# LT8315TestBoard.net
KiCad netlist of a schematic drawn in Altium Designer
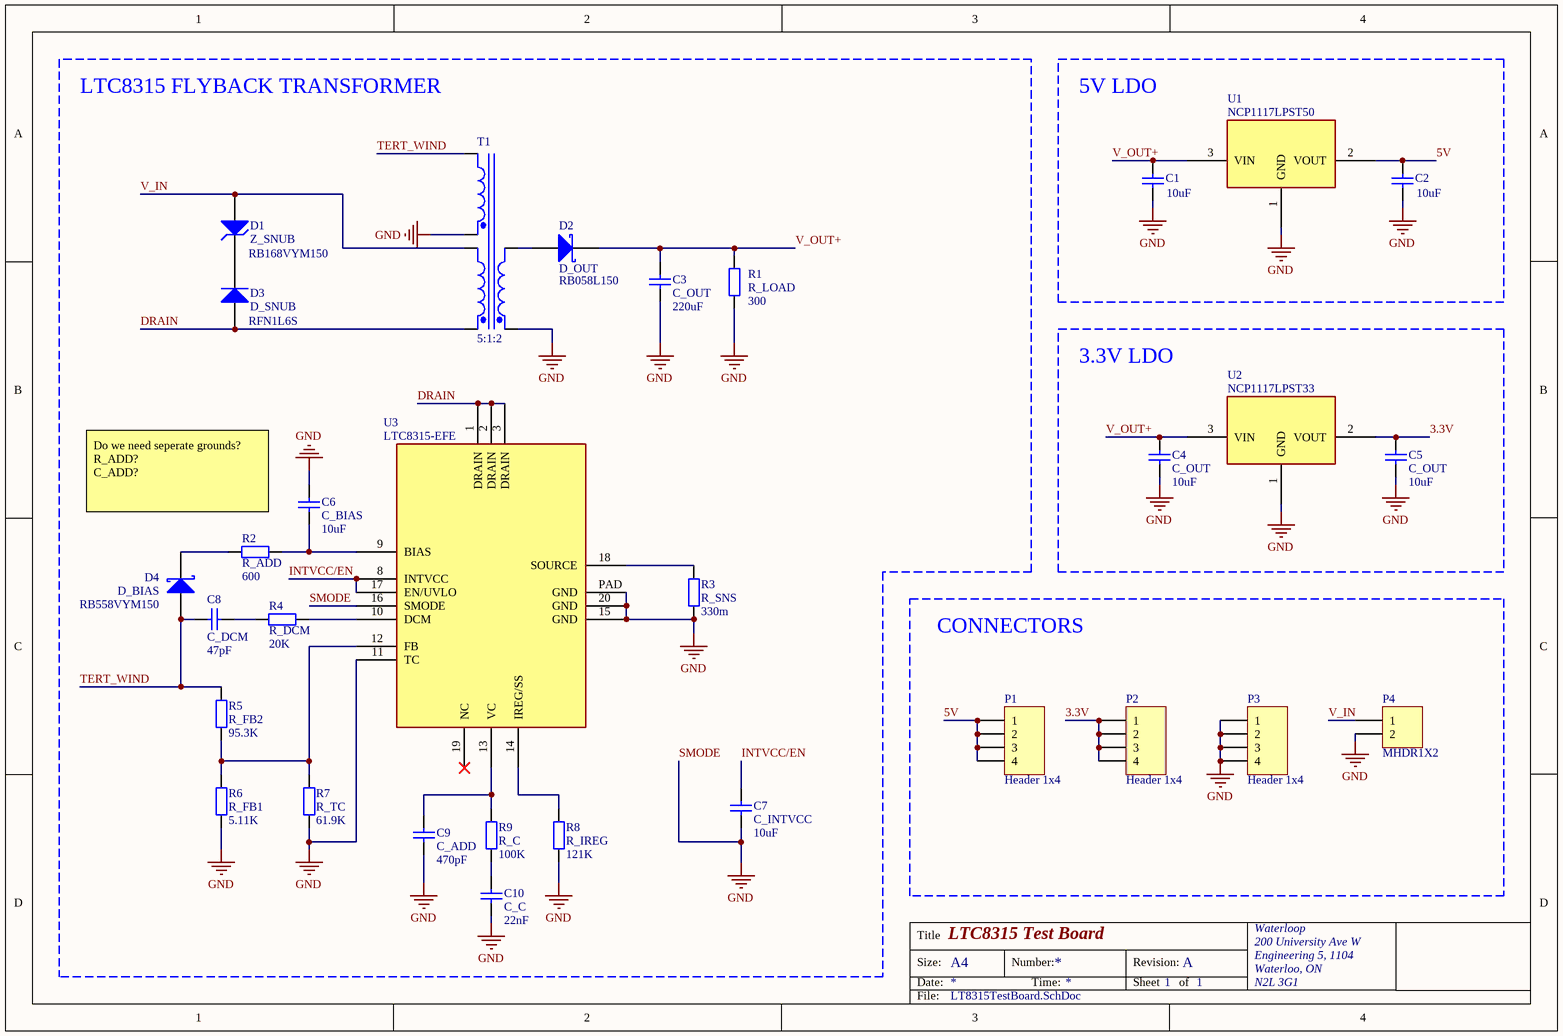
[diagram p0: LT8315TestBoard.SchDoc]

(export (version "E")
  (design (tool "Eeschema 10.0.6"))
  (components
    (comp (ref "C1")
      (value "10uF")
      (footprint "RAD-0.3")
      (description "Capacitor")
      (fields (field (name "Comment") "C_OUT") (field (name "PUBLISHER") "Altium Limited"))
      (libsource (lib "Miscellaneous Devices") (part "Cap"))
    )
    (comp (ref "C2")
      (value "10uF")
      (footprint "RAD-0.3")
      (description "Capacitor")
      (fields (field (name "Comment") "C_OUT") (field (name "PUBLISHER") "Altium Limited"))
      (libsource (lib "Miscellaneous Devices") (part "Cap"))
    )
    (comp (ref "C3")
      (value "C_OUT")
      (footprint "RAD-0.3")
      (description "Capacitor")
      (fields (field (name "ALTIUM_VALUE") "220uF") (field (name "PUBLISHER") "Altium Limited"))
      (libsource (lib "Miscellaneous Devices") (part "Cap"))
    )
    (comp (ref "C4")
      (value "C_OUT")
      (footprint "RAD-0.3")
      (description "Capacitor")
      (fields (field (name "ALTIUM_VALUE") "10uF") (field (name "PUBLISHER") "Altium Limited"))
      (libsource (lib "Miscellaneous Devices") (part "Cap"))
    )
    (comp (ref "C5")
      (value "C_OUT")
      (footprint "RAD-0.3")
      (description "Capacitor")
      (fields (field (name "ALTIUM_VALUE") "10uF") (field (name "PUBLISHER") "Altium Limited"))
      (libsource (lib "Miscellaneous Devices") (part "Cap"))
    )
    (comp (ref "C6")
      (value "C_BIAS")
      (footprint "RAD-0.3")
      (description "Capacitor")
      (fields (field (name "ALTIUM_VALUE") "10uF") (field (name "PUBLISHER") "Altium Limited"))
      (libsource (lib "Miscellaneous Devices") (part "Cap"))
    )
    (comp (ref "C7")
      (value "C_INTVCC")
      (footprint "RAD-0.3")
      (description "Capacitor")
      (fields (field (name "ALTIUM_VALUE") "10uF") (field (name "PUBLISHER") "Altium Limited"))
      (libsource (lib "Miscellaneous Devices") (part "Cap"))
    )
    (comp (ref "C8")
      (value "C_DCM")
      (footprint "RAD-0.3")
      (description "Capacitor")
      (fields (field (name "ALTIUM_VALUE") "47pF") (field (name "PUBLISHER") "Altium Limited"))
      (libsource (lib "Miscellaneous Devices") (part "Cap"))
    )
    (comp (ref "C9")
      (value "C_ADD")
      (footprint "RAD-0.3")
      (description "Capacitor")
      (fields (field (name "ALTIUM_VALUE") "470pF") (field (name "PUBLISHER") "Altium Limited"))
      (libsource (lib "Miscellaneous Devices") (part "Cap"))
    )
    (comp (ref "C10")
      (value "C_C")
      (footprint "RAD-0.3")
      (description "Capacitor")
      (fields (field (name "ALTIUM_VALUE") "22nF") (field (name "PUBLISHER") "Altium Limited"))
      (libsource (lib "Miscellaneous Devices") (part "Cap"))
    )
    (comp (ref "D1")
      (value "Z_SNUB")
      (footprint "DIODE-0.7")
      (description "Zener Diode")
      (fields (field (name "PARTNUMBER") "RB168VYM150") (field (name "PUBLISHER") "Altium Limited"))
      (libsource (lib "Miscellaneous Devices") (part "D Zener"))
    )
    (comp (ref "D2")
      (value "D_OUT")
      (footprint "SMB")
      (description "Schottky Diode")
      (fields (field (name "PARTNUMBER") "RB058L150") (field (name "PUBLISHER") "Altium Limited"))
      (libsource (lib "Miscellaneous Devices") (part "D Schottky"))
    )
    (comp (ref "D3")
      (value "D_SNUB")
      (footprint "SMC")
      (description "Default Diode")
      (fields (field (name "PARTNUMBER") "RFN1L6S") (field (name "PUBLISHER") "Altium Limited"))
      (libsource (lib "Miscellaneous Devices") (part "Diode"))
    )
    (comp (ref "D4")
      (value "D_BIAS")
      (footprint "SMB")
      (description "Schottky Diode")
      (fields (field (name "PARTNUMBER") "RB558VYM150") (field (name "PUBLISHER") "Altium Limited"))
      (libsource (lib "Miscellaneous Devices") (part "D Schottky"))
    )
    (comp (ref "P1")
      (value "Header 1x4")
      (footprint "HDR1X4")
      (description "Header, 4-Pin")
      (fields (field (name "PUBLISHER") "Altium Limited"))
      (libsource (lib "Miscellaneous Connectors") (part "Header 4"))
    )
    (comp (ref "P2")
      (value "Header 1x4")
      (footprint "HDR1X4")
      (description "Header, 4-Pin")
      (fields (field (name "PUBLISHER") "Altium Limited"))
      (libsource (lib "Miscellaneous Connectors") (part "Header 4"))
    )
    (comp (ref "P3")
      (value "Header 1x4")
      (footprint "HDR1X4")
      (description "Header, 4-Pin")
      (fields (field (name "PUBLISHER") "Altium Limited"))
      (libsource (lib "Miscellaneous Connectors") (part "Header 4"))
    )
    (comp (ref "P4")
      (value "MHDR1X2")
      (footprint "MHDR1X2")
      (description "Header, 2-Pin")
      (fields (field (name "PUBLISHER") "Altium Limited"))
      (libsource (lib "Miscellaneous Connectors") (part "MHDR1X2"))
    )
    (comp (ref "R1")
      (value "R_LOAD")
      (footprint "AXIAL-0.4")
      (description "Resistor")
      (fields (field (name "ALTIUM_VALUE") "300") (field (name "PUBLISHER") "Altium Limited"))
      (libsource (lib "Miscellaneous Devices") (part "Res2"))
    )
    (comp (ref "R2")
      (value "R_ADD")
      (footprint "AXIAL-0.4")
      (description "Resistor")
      (fields (field (name "ALTIUM_VALUE") "600") (field (name "PUBLISHER") "Altium Limited"))
      (libsource (lib "") (part "Res2_1"))
    )
    (comp (ref "R3")
      (value "R_SNS")
      (footprint "AXIAL-0.4")
      (description "Resistor")
      (fields (field (name "ALTIUM_VALUE") "330m") (field (name "PUBLISHER") "Altium Limited"))
      (libsource (lib "Miscellaneous Devices") (part "Res2"))
    )
    (comp (ref "R4")
      (value "R_DCM")
      (footprint "AXIAL-0.4")
      (description "Resistor")
      (fields (field (name "ALTIUM_VALUE") "20K") (field (name "PUBLISHER") "Altium Limited"))
      (libsource (lib "") (part "Res2_1"))
    )
    (comp (ref "R5")
      (value "R_FB2")
      (footprint "AXIAL-0.4")
      (description "Resistor")
      (fields (field (name "ALTIUM_VALUE") "95.3K") (field (name "PUBLISHER") "Altium Limited"))
      (libsource (lib "Miscellaneous Devices") (part "Res2"))
    )
    (comp (ref "R6")
      (value "R_FB1")
      (footprint "AXIAL-0.4")
      (description "Resistor")
      (fields (field (name "ALTIUM_VALUE") "5.11K") (field (name "PUBLISHER") "Altium Limited"))
      (libsource (lib "Miscellaneous Devices") (part "Res2"))
    )
    (comp (ref "R7")
      (value "R_TC")
      (footprint "AXIAL-0.4")
      (description "Resistor")
      (fields (field (name "ALTIUM_VALUE") "61.9K") (field (name "PUBLISHER") "Altium Limited"))
      (libsource (lib "Miscellaneous Devices") (part "Res2"))
    )
    (comp (ref "R8")
      (value "R_IREG")
      (footprint "AXIAL-0.4")
      (description "Resistor")
      (fields (field (name "ALTIUM_VALUE") "121K") (field (name "PUBLISHER") "Altium Limited"))
      (libsource (lib "Miscellaneous Devices") (part "Res2"))
    )
    (comp (ref "R9")
      (value "R_C")
      (footprint "AXIAL-0.4")
      (description "Resistor")
      (fields (field (name "ALTIUM_VALUE") "100K") (field (name "PUBLISHER") "Altium Limited"))
      (libsource (lib "Miscellaneous Devices") (part "Res2"))
    )
    (comp (ref "T1")
      (value "5:1:2")
      (footprint "TRF_6")
      (description "Three-winding Transformer (Non-Ideal)")
      (fields (field (name "PUBLISHER") "Altium Limited"))
      (libsource (lib "Miscellaneous Devices") (part "Trans3"))
    )
    (comp (ref "U1") (value "NCP1117LPST50") (libsource (lib "LTC8315") (part "NCP1117LPST50")))
    (comp (ref "U2") (value "NCP1117LPST33") (libsource (lib "LTC8315") (part "NCP1117LPST33")))
    (comp (ref "U3") (value "LTC8315-EFE") (libsource (lib "LTC8315") (part "LTC8315-EFE")))
  )
  (nets
    (net (code "1") (name "/3.3V") (class "Default")
      (node (ref "C5") (pin "2") (pinfunction "2_2") (pintype "passive"))
      (node (ref "P2") (pin "1") (pinfunction "1_1") (pintype "passive"))
      (node (ref "P2") (pin "2") (pinfunction "2_2") (pintype "passive"))
      (node (ref "P2") (pin "3") (pinfunction "3_3") (pintype "passive"))
      (node (ref "P2") (pin "4") (pinfunction "4_4") (pintype "passive"))
      (node (ref "U2") (pin "2") (pinfunction "VOUT_2") (pintype "passive"))
    )
    (net (code "2") (name "/5V") (class "Default")
      (node (ref "C2") (pin "2") (pinfunction "2_2") (pintype "passive"))
      (node (ref "P1") (pin "1") (pinfunction "1_1") (pintype "passive"))
      (node (ref "P1") (pin "2") (pinfunction "2_2") (pintype "passive"))
      (node (ref "P1") (pin "3") (pinfunction "3_3") (pintype "passive"))
      (node (ref "P1") (pin "4") (pinfunction "4_4") (pintype "passive"))
      (node (ref "U1") (pin "2") (pinfunction "VOUT_2") (pintype "passive"))
    )
    (net (code "3") (name "/DRAIN") (class "Default")
      (node (ref "D3") (pin "1") (pinfunction "A_1") (pintype "passive"))
      (node (ref "T1") (pin "3") (pinfunction "Sec1+_3") (pintype "passive"))
      (node (ref "U3") (pin "1") (pinfunction "DRAIN_1") (pintype "passive"))
      (node (ref "U3") (pin "2") (pinfunction "DRAIN_2") (pintype "passive"))
      (node (ref "U3") (pin "3") (pinfunction "DRAIN_3") (pintype "passive"))
    )
    (net (code "4") (name "/INTVCC{slash}EN") (class "Default")
      (node (ref "C7") (pin "1") (pinfunction "1_1") (pintype "passive"))
      (node (ref "U3") (pin "17") (pinfunction "EN/UVLO_17") (pintype "passive"))
      (node (ref "U3") (pin "8") (pinfunction "INTVCC_8") (pintype "passive"))
    )
    (net (code "5") (name "/TERT_WIND") (class "Default")
      (node (ref "C8") (pin "1") (pinfunction "1_1") (pintype "passive"))
      (node (ref "D4") (pin "1") (pinfunction "A_1") (pintype "passive"))
      (node (ref "R5") (pin "2") (pinfunction "2_2") (pintype "passive"))
      (node (ref "T1") (pin "6") (pinfunction "Sec2-_6") (pintype "passive"))
    )
    (net (code "6") (name "/V_IN") (class "Default")
      (node (ref "D1") (pin "1") (pinfunction "A_1") (pintype "passive"))
      (node (ref "P4") (pin "1") (pinfunction "1_1") (pintype "passive"))
      (node (ref "T1") (pin "4") (pinfunction "Sec1-_4") (pintype "passive"))
    )
    (net (code "7") (name "/V_OUT+") (class "Default")
      (node (ref "C1") (pin "2") (pinfunction "2_2") (pintype "passive"))
      (node (ref "C3") (pin "2") (pinfunction "2_2") (pintype "passive"))
      (node (ref "C4") (pin "2") (pinfunction "2_2") (pintype "passive"))
      (node (ref "D2") (pin "2") (pinfunction "K_2") (pintype "passive"))
      (node (ref "R1") (pin "2") (pinfunction "2_2") (pintype "passive"))
      (node (ref "U1") (pin "3") (pinfunction "VIN_3") (pintype "passive"))
      (node (ref "U2") (pin "3") (pinfunction "VIN_3") (pintype "passive"))
    )
    (net (code "8") (name "GND") (class "Default")
      (node (ref "C1") (pin "1") (pinfunction "1_1") (pintype "passive"))
      (node (ref "C10") (pin "1") (pinfunction "1_1") (pintype "passive"))
      (node (ref "C2") (pin "1") (pinfunction "1_1") (pintype "passive"))
      (node (ref "C3") (pin "1") (pinfunction "1_1") (pintype "passive"))
      (node (ref "C4") (pin "1") (pinfunction "1_1") (pintype "passive"))
      (node (ref "C5") (pin "1") (pinfunction "1_1") (pintype "passive"))
      (node (ref "C6") (pin "1") (pinfunction "1_1") (pintype "passive"))
      (node (ref "C7") (pin "2") (pinfunction "2_2") (pintype "passive"))
      (node (ref "C9") (pin "1") (pinfunction "1_1") (pintype "passive"))
      (node (ref "P3") (pin "1") (pinfunction "1_1") (pintype "passive"))
      (node (ref "P3") (pin "2") (pinfunction "2_2") (pintype "passive"))
      (node (ref "P3") (pin "3") (pinfunction "3_3") (pintype "passive"))
      (node (ref "P3") (pin "4") (pinfunction "4_4") (pintype "passive"))
      (node (ref "P4") (pin "2") (pinfunction "2_2") (pintype "passive"))
      (node (ref "R1") (pin "1") (pinfunction "1_1") (pintype "passive"))
      (node (ref "R3") (pin "1") (pinfunction "1_1") (pintype "passive"))
      (node (ref "R6") (pin "1") (pinfunction "1_1") (pintype "passive"))
      (node (ref "R7") (pin "1") (pinfunction "1_1") (pintype "passive"))
      (node (ref "R8") (pin "1") (pinfunction "1_1") (pintype "passive"))
      (node (ref "T1") (pin "1") (pinfunction "Pri+_1") (pintype "passive"))
      (node (ref "T1") (pin "5") (pinfunction "Sec2+_5") (pintype "passive"))
      (node (ref "U1") (pin "1") (pinfunction "GND_1") (pintype "passive"))
      (node (ref "U2") (pin "1") (pinfunction "GND_1") (pintype "passive"))
      (node (ref "U3") (pin "11") (pinfunction "TC_11") (pintype "passive"))
      (node (ref "U3") (pin "15") (pinfunction "GND_15") (pintype "passive"))
      (node (ref "U3") (pin "16") (pinfunction "SMODE_16") (pintype "passive"))
      (node (ref "U3") (pin "20") (pinfunction "GND_20") (pintype "passive"))
      (node (ref "U3") (pin "PAD") (pinfunction "GND_PAD") (pintype "passive"))
    )
    (net (code "9") (name "Net-(C8-Pad2)") (class "Default")
      (node (ref "C8") (pin "2") (pinfunction "2_2") (pintype "passive"))
      (node (ref "R4") (pin "2") (pinfunction "2_2") (pintype "passive"))
    )
    (net (code "10") (name "Net-(C10-Pad2)") (class "Default")
      (node (ref "C10") (pin "2") (pinfunction "2_2") (pintype "passive"))
      (node (ref "R9") (pin "1") (pinfunction "1_1") (pintype "passive"))
    )
    (net (code "11") (name "Net-(D1-K)") (class "Default")
      (node (ref "D1") (pin "2") (pinfunction "K_2") (pintype "passive"))
      (node (ref "D3") (pin "2") (pinfunction "K_2") (pintype "passive"))
    )
    (net (code "12") (name "Net-(D2-A)") (class "Default")
      (node (ref "D2") (pin "1") (pinfunction "A_1") (pintype "passive"))
      (node (ref "T1") (pin "2") (pinfunction "Pri-_2") (pintype "passive"))
    )
    (net (code "13") (name "Net-(D4-K)") (class "Default")
      (node (ref "D4") (pin "2") (pinfunction "K_2") (pintype "passive"))
      (node (ref "R2") (pin "2") (pinfunction "2_2") (pintype "passive"))
    )
    (net (code "14") (name "Net-(U3-BIAS)") (class "Default")
      (node (ref "C6") (pin "2") (pinfunction "2_2") (pintype "passive"))
      (node (ref "R2") (pin "1") (pinfunction "1_1") (pintype "passive"))
      (node (ref "U3") (pin "9") (pinfunction "BIAS_9") (pintype "passive"))
    )
    (net (code "15") (name "Net-(U3-DCM)") (class "Default")
      (node (ref "R4") (pin "1") (pinfunction "1_1") (pintype "passive"))
      (node (ref "U3") (pin "10") (pinfunction "DCM_10") (pintype "passive"))
    )
    (net (code "16") (name "Net-(U3-FB)") (class "Default")
      (node (ref "R5") (pin "1") (pinfunction "1_1") (pintype "passive"))
      (node (ref "R6") (pin "2") (pinfunction "2_2") (pintype "passive"))
      (node (ref "R7") (pin "2") (pinfunction "2_2") (pintype "passive"))
      (node (ref "U3") (pin "12") (pinfunction "FB_12") (pintype "passive"))
    )
    (net (code "17") (name "Net-(U3-IREG{slash}SS)") (class "Default")
      (node (ref "R8") (pin "2") (pinfunction "2_2") (pintype "passive"))
      (node (ref "U3") (pin "14") (pinfunction "IREG/SS_14") (pintype "passive"))
    )
    (net (code "18") (name "Net-(U3-SOURCE)") (class "Default")
      (node (ref "R3") (pin "2") (pinfunction "2_2") (pintype "passive"))
      (node (ref "U3") (pin "18") (pinfunction "SOURCE_18") (pintype "passive"))
    )
    (net (code "19") (name "Net-(U3-VC)") (class "Default")
      (node (ref "C9") (pin "2") (pinfunction "2_2") (pintype "passive"))
      (node (ref "R9") (pin "2") (pinfunction "2_2") (pintype "passive"))
      (node (ref "U3") (pin "13") (pinfunction "VC_13") (pintype "passive"))
    )
    (net (code "20") (name "unconnected-(U3-NC-Pad19)") (class "Default")
      (node (ref "U3") (pin "19") (pinfunction "NC_19") (pintype "passive+no_connect"))
    )
  )
)
